# piezo-driver_v0_2-R001.net
KiCad netlist of a schematic drawn in EAGLE
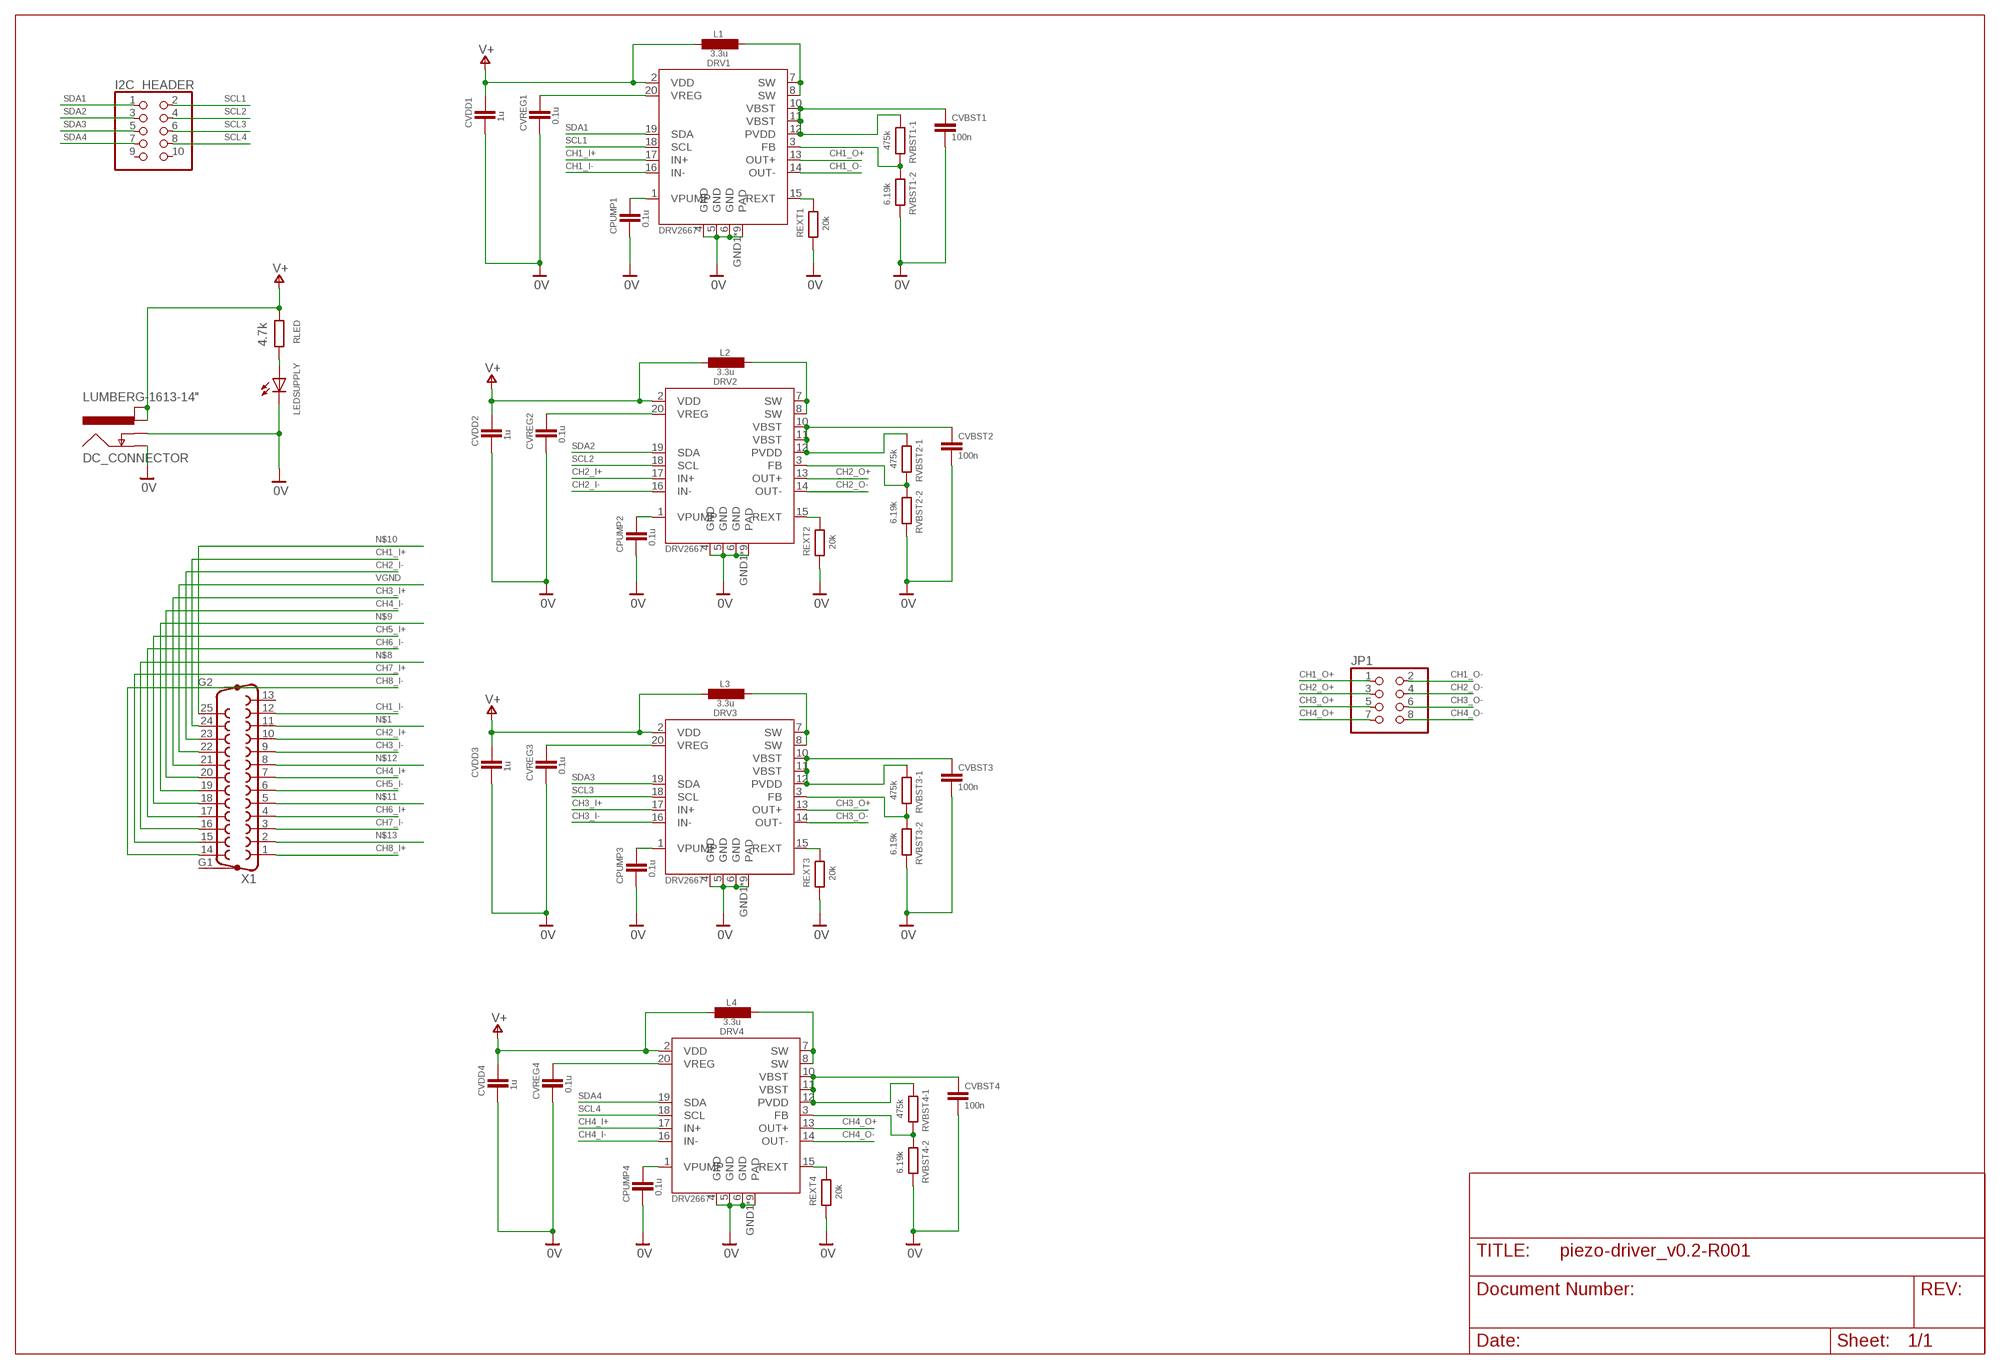
[diagram p0: schematic, sheet 1]

(export (version "E")
  (design (tool "Eeschema 10.0.6"))
  (components
    (comp (ref "CPUMP1")
      (value "0.1u")
      (footprint "eagle-import:C0805")
      (libsource (lib "eagle-import") (part "C-EUC0805"))
    )
    (comp (ref "CPUMP2")
      (value "0.1u")
      (footprint "eagle-import:C0805")
      (libsource (lib "eagle-import") (part "C-EUC0805"))
    )
    (comp (ref "CPUMP3")
      (value "0.1u")
      (footprint "eagle-import:C0805")
      (libsource (lib "eagle-import") (part "C-EUC0805"))
    )
    (comp (ref "CPUMP4")
      (value "0.1u")
      (footprint "eagle-import:C0805")
      (libsource (lib "eagle-import") (part "C-EUC0805"))
    )
    (comp (ref "CVBST1")
      (value "100n")
      (footprint "eagle-import:C0805")
      (libsource (lib "eagle-import") (part "C-EUC0805"))
    )
    (comp (ref "CVBST2")
      (value "100n")
      (footprint "eagle-import:C0805")
      (libsource (lib "eagle-import") (part "C-EUC0805"))
    )
    (comp (ref "CVBST3")
      (value "100n")
      (footprint "eagle-import:C0805")
      (libsource (lib "eagle-import") (part "C-EUC0805"))
    )
    (comp (ref "CVBST4")
      (value "100n")
      (footprint "eagle-import:C0805")
      (libsource (lib "eagle-import") (part "C-EUC0805"))
    )
    (comp (ref "CVDD1")
      (value "1u")
      (footprint "eagle-import:C0805")
      (libsource (lib "eagle-import") (part "C-EUC0805"))
    )
    (comp (ref "CVDD2")
      (value "1u")
      (footprint "eagle-import:C0805")
      (libsource (lib "eagle-import") (part "C-EUC0805"))
    )
    (comp (ref "CVDD3")
      (value "1u")
      (footprint "eagle-import:C0805")
      (libsource (lib "eagle-import") (part "C-EUC0805"))
    )
    (comp (ref "CVDD4")
      (value "1u")
      (footprint "eagle-import:C0805")
      (libsource (lib "eagle-import") (part "C-EUC0805"))
    )
    (comp (ref "CVREG1")
      (value "0.1u")
      (footprint "eagle-import:C0805")
      (libsource (lib "eagle-import") (part "C-EUC0805"))
    )
    (comp (ref "CVREG2")
      (value "0.1u")
      (footprint "eagle-import:C0805")
      (libsource (lib "eagle-import") (part "C-EUC0805"))
    )
    (comp (ref "CVREG3")
      (value "0.1u")
      (footprint "eagle-import:C0805")
      (libsource (lib "eagle-import") (part "C-EUC0805"))
    )
    (comp (ref "CVREG4")
      (value "0.1u")
      (footprint "eagle-import:C0805")
      (libsource (lib "eagle-import") (part "C-EUC0805"))
    )
    (comp (ref "DC_CONNECTOR")
      (value "LUMBERG-1613-14\"")
      (footprint "eagle-import:LUMBERG-1613_14")
      (libsource (lib "eagle-import") (part "LUMBERG-1613-14{dblquote}"))
    )
    (comp (ref "DRV1")
      (value "DRV2667QFN")
      (footprint "eagle-import:QFN400X400")
      (libsource (lib "eagle-import") (part "DRV2667QFN"))
    )
    (comp (ref "DRV2")
      (value "DRV2667QFN")
      (footprint "eagle-import:QFN400X400")
      (libsource (lib "eagle-import") (part "DRV2667QFN"))
    )
    (comp (ref "DRV3")
      (value "DRV2667QFN")
      (footprint "eagle-import:QFN400X400")
      (libsource (lib "eagle-import") (part "DRV2667QFN"))
    )
    (comp (ref "DRV4")
      (value "DRV2667QFN")
      (footprint "eagle-import:QFN400X400")
      (libsource (lib "eagle-import") (part "DRV2667QFN"))
    )
    (comp (ref "I2C_HEADER")
      (value "HEADER_2X52.54_FEMALE")
      (footprint "eagle-import:2X05_2.54")
      (libsource (lib "eagle-import") (part "HEADER_2X52.54_FEMALE"))
    )
    (comp (ref "JP1")
      (value "PINHD-2X4/90")
      (footprint "eagle-import:2X04_90")
      (libsource (lib "eagle-import") (part "PINHD-2X4/90"))
    )
    (comp (ref "L1")
      (value "3.3u")
      (footprint "eagle-import:L3225M")
      (libsource (lib "eagle-import") (part "L-EUL3225M"))
    )
    (comp (ref "L2")
      (value "3.3u")
      (footprint "eagle-import:L3225M")
      (libsource (lib "eagle-import") (part "L-EUL3225M"))
    )
    (comp (ref "L3")
      (value "3.3u")
      (footprint "eagle-import:L3225M")
      (libsource (lib "eagle-import") (part "L-EUL3225M"))
    )
    (comp (ref "L4")
      (value "3.3u")
      (footprint "eagle-import:L3225M")
      (libsource (lib "eagle-import") (part "L-EUL3225M"))
    )
    (comp (ref "LEDSUPPLY")
      (value "LED0603")
      (footprint "eagle-import:LED-0603")
      (libsource (lib "eagle-import") (part "LED0603"))
    )
    (comp (ref "REXT1")
      (value "20k")
      (footprint "eagle-import:R0805")
      (libsource (lib "eagle-import") (part "R-EU_R0805"))
    )
    (comp (ref "REXT2")
      (value "20k")
      (footprint "eagle-import:R0805")
      (libsource (lib "eagle-import") (part "R-EU_R0805"))
    )
    (comp (ref "REXT3")
      (value "20k")
      (footprint "eagle-import:R0805")
      (libsource (lib "eagle-import") (part "R-EU_R0805"))
    )
    (comp (ref "REXT4")
      (value "20k")
      (footprint "eagle-import:R0805")
      (libsource (lib "eagle-import") (part "R-EU_R0805"))
    )
    (comp (ref "RLED")
      (value "4.7k")
      (footprint "eagle-import:R0805")
      (libsource (lib "eagle-import") (part "rcl_R-EU_R0805"))
    )
    (comp (ref "RVBST1-1")
      (value "475k")
      (footprint "eagle-import:R0805")
      (libsource (lib "eagle-import") (part "R-EU_R0805"))
    )
    (comp (ref "RVBST1-2")
      (value "6.19k")
      (footprint "eagle-import:R0805")
      (libsource (lib "eagle-import") (part "R-EU_R0805"))
    )
    (comp (ref "RVBST2-1")
      (value "475k")
      (footprint "eagle-import:R0805")
      (libsource (lib "eagle-import") (part "R-EU_R0805"))
    )
    (comp (ref "RVBST2-2")
      (value "6.19k")
      (footprint "eagle-import:R0805")
      (libsource (lib "eagle-import") (part "R-EU_R0805"))
    )
    (comp (ref "RVBST3-1")
      (value "475k")
      (footprint "eagle-import:R0805")
      (libsource (lib "eagle-import") (part "R-EU_R0805"))
    )
    (comp (ref "RVBST3-2")
      (value "6.19k")
      (footprint "eagle-import:R0805")
      (libsource (lib "eagle-import") (part "R-EU_R0805"))
    )
    (comp (ref "RVBST4-1")
      (value "475k")
      (footprint "eagle-import:R0805")
      (libsource (lib "eagle-import") (part "R-EU_R0805"))
    )
    (comp (ref "RVBST4-2")
      (value "6.19k")
      (footprint "eagle-import:R0805")
      (libsource (lib "eagle-import") (part "R-EU_R0805"))
    )
    (comp (ref "X1")
      (value "F25HP")
      (footprint "eagle-import:F25HP")
      (libsource (lib "eagle-import") (part "F25HP"))
    )
  )
  (nets
    (net (code "1") (name "/CH1_I+") (class "Default")
      (node (ref "DRV1") (pin "17") (pinfunction "IN+_17") (pintype "bidirectional"))
      (node (ref "X1") (pin "24") (pinfunction "24_24") (pintype "passive"))
    )
    (net (code "2") (name "/CH1_I-") (class "Default")
      (node (ref "DRV1") (pin "16") (pinfunction "IN-_16") (pintype "bidirectional"))
      (node (ref "X1") (pin "12") (pinfunction "12_12") (pintype "passive"))
    )
    (net (code "3") (name "/CH1_O+") (class "Default")
      (node (ref "DRV1") (pin "13") (pinfunction "OUT+_13") (pintype "bidirectional"))
      (node (ref "JP1") (pin "1") (pinfunction "1_1") (pintype "passive"))
    )
    (net (code "4") (name "/CH1_O-") (class "Default")
      (node (ref "DRV1") (pin "14") (pinfunction "OUT-_14") (pintype "bidirectional"))
      (node (ref "JP1") (pin "2") (pinfunction "2_2") (pintype "passive"))
    )
    (net (code "5") (name "/CH2_I+") (class "Default")
      (node (ref "DRV2") (pin "17") (pinfunction "IN+_17") (pintype "bidirectional"))
      (node (ref "X1") (pin "10") (pinfunction "10_10") (pintype "passive"))
    )
    (net (code "6") (name "/CH2_I-") (class "Default")
      (node (ref "DRV2") (pin "16") (pinfunction "IN-_16") (pintype "bidirectional"))
      (node (ref "X1") (pin "23") (pinfunction "23_23") (pintype "passive"))
    )
    (net (code "7") (name "/CH2_O+") (class "Default")
      (node (ref "DRV2") (pin "13") (pinfunction "OUT+_13") (pintype "bidirectional"))
      (node (ref "JP1") (pin "3") (pinfunction "3_3") (pintype "passive"))
    )
    (net (code "8") (name "/CH2_O-") (class "Default")
      (node (ref "DRV2") (pin "14") (pinfunction "OUT-_14") (pintype "bidirectional"))
      (node (ref "JP1") (pin "4") (pinfunction "4_4") (pintype "passive"))
    )
    (net (code "9") (name "/CH3_I+") (class "Default")
      (node (ref "DRV3") (pin "17") (pinfunction "IN+_17") (pintype "bidirectional"))
      (node (ref "X1") (pin "21") (pinfunction "21_21") (pintype "passive"))
    )
    (net (code "10") (name "/CH3_I-") (class "Default")
      (node (ref "DRV3") (pin "16") (pinfunction "IN-_16") (pintype "bidirectional"))
      (node (ref "X1") (pin "9") (pinfunction "9_9") (pintype "passive"))
    )
    (net (code "11") (name "/CH3_O+") (class "Default")
      (node (ref "DRV3") (pin "13") (pinfunction "OUT+_13") (pintype "bidirectional"))
      (node (ref "JP1") (pin "5") (pinfunction "5_5") (pintype "passive"))
    )
    (net (code "12") (name "/CH3_O-") (class "Default")
      (node (ref "DRV3") (pin "14") (pinfunction "OUT-_14") (pintype "bidirectional"))
      (node (ref "JP1") (pin "6") (pinfunction "6_6") (pintype "passive"))
    )
    (net (code "13") (name "/CH4_I+") (class "Default")
      (node (ref "DRV4") (pin "17") (pinfunction "IN+_17") (pintype "bidirectional"))
      (node (ref "X1") (pin "7") (pinfunction "7_7") (pintype "passive"))
    )
    (net (code "14") (name "/CH4_I-") (class "Default")
      (node (ref "DRV4") (pin "16") (pinfunction "IN-_16") (pintype "bidirectional"))
      (node (ref "X1") (pin "20") (pinfunction "20_20") (pintype "passive"))
    )
    (net (code "15") (name "/CH4_O+") (class "Default")
      (node (ref "DRV4") (pin "13") (pinfunction "OUT+_13") (pintype "bidirectional"))
      (node (ref "JP1") (pin "7") (pinfunction "7_7") (pintype "passive"))
    )
    (net (code "16") (name "/CH4_O-") (class "Default")
      (node (ref "DRV4") (pin "14") (pinfunction "OUT-_14") (pintype "bidirectional"))
      (node (ref "JP1") (pin "8") (pinfunction "8_8") (pintype "passive"))
    )
    (net (code "17") (name "/CH5_I+") (class "Default")
      (node (ref "X1") (pin "18") (pinfunction "18_18") (pintype "passive"))
    )
    (net (code "18") (name "/CH5_I-") (class "Default")
      (node (ref "X1") (pin "6") (pinfunction "6_6") (pintype "passive"))
    )
    (net (code "19") (name "/CH6_I+") (class "Default")
      (node (ref "X1") (pin "4") (pinfunction "4_4") (pintype "passive"))
    )
    (net (code "20") (name "/CH6_I-") (class "Default")
      (node (ref "X1") (pin "17") (pinfunction "17_17") (pintype "passive"))
    )
    (net (code "21") (name "/CH7_I+") (class "Default")
      (node (ref "X1") (pin "15") (pinfunction "15_15") (pintype "passive"))
    )
    (net (code "22") (name "/CH7_I-") (class "Default")
      (node (ref "X1") (pin "3") (pinfunction "3_3") (pintype "passive"))
    )
    (net (code "23") (name "/CH8_I+") (class "Default")
      (node (ref "X1") (pin "1") (pinfunction "1_1") (pintype "passive"))
    )
    (net (code "24") (name "/CH8_I-") (class "Default")
      (node (ref "X1") (pin "14") (pinfunction "14_14") (pintype "passive"))
    )
    (net (code "25") (name "/N$1") (class "Default")
      (node (ref "X1") (pin "11") (pinfunction "11_11") (pintype "passive"))
    )
    (net (code "26") (name "/N$8") (class "Default")
      (node (ref "X1") (pin "16") (pinfunction "16_16") (pintype "passive"))
    )
    (net (code "27") (name "/N$9") (class "Default")
      (node (ref "X1") (pin "19") (pinfunction "19_19") (pintype "passive"))
    )
    (net (code "28") (name "/N$10") (class "Default")
      (node (ref "X1") (pin "25") (pinfunction "25_25") (pintype "passive"))
    )
    (net (code "29") (name "/N$11") (class "Default")
      (node (ref "X1") (pin "5") (pinfunction "5_5") (pintype "passive"))
    )
    (net (code "30") (name "/N$12") (class "Default")
      (node (ref "X1") (pin "8") (pinfunction "8_8") (pintype "passive"))
    )
    (net (code "31") (name "/N$13") (class "Default")
      (node (ref "X1") (pin "2") (pinfunction "2_2") (pintype "passive"))
    )
    (net (code "32") (name "/SCL1") (class "Default")
      (node (ref "DRV1") (pin "18") (pinfunction "SCL_18") (pintype "bidirectional"))
      (node (ref "I2C_HEADER") (pin "2") (pinfunction "2_2") (pintype "passive"))
    )
    (net (code "33") (name "/SCL2") (class "Default")
      (node (ref "DRV2") (pin "18") (pinfunction "SCL_18") (pintype "bidirectional"))
      (node (ref "I2C_HEADER") (pin "4") (pinfunction "4_4") (pintype "passive"))
    )
    (net (code "34") (name "/SCL3") (class "Default")
      (node (ref "DRV3") (pin "18") (pinfunction "SCL_18") (pintype "bidirectional"))
      (node (ref "I2C_HEADER") (pin "6") (pinfunction "6_6") (pintype "passive"))
    )
    (net (code "35") (name "/SCL4") (class "Default")
      (node (ref "DRV4") (pin "18") (pinfunction "SCL_18") (pintype "bidirectional"))
      (node (ref "I2C_HEADER") (pin "8") (pinfunction "8_8") (pintype "passive"))
    )
    (net (code "36") (name "/SDA1") (class "Default")
      (node (ref "DRV1") (pin "19") (pinfunction "SDA_19") (pintype "bidirectional"))
      (node (ref "I2C_HEADER") (pin "1") (pinfunction "1_1") (pintype "passive"))
    )
    (net (code "37") (name "/SDA2") (class "Default")
      (node (ref "DRV2") (pin "19") (pinfunction "SDA_19") (pintype "bidirectional"))
      (node (ref "I2C_HEADER") (pin "3") (pinfunction "3_3") (pintype "passive"))
    )
    (net (code "38") (name "/SDA3") (class "Default")
      (node (ref "DRV3") (pin "19") (pinfunction "SDA_19") (pintype "bidirectional"))
      (node (ref "I2C_HEADER") (pin "5") (pinfunction "5_5") (pintype "passive"))
    )
    (net (code "39") (name "/SDA4") (class "Default")
      (node (ref "DRV4") (pin "19") (pinfunction "SDA_19") (pintype "bidirectional"))
      (node (ref "I2C_HEADER") (pin "7") (pinfunction "7_7") (pintype "passive"))
    )
    (net (code "40") (name "/VGND") (class "Default")
      (node (ref "X1") (pin "22") (pinfunction "22_22") (pintype "passive"))
    )
    (net (code "41") (name "0V") (class "Default")
      (node (ref "CPUMP1") (pin "2") (pinfunction "2_2") (pintype "passive"))
      (node (ref "CPUMP2") (pin "2") (pinfunction "2_2") (pintype "passive"))
      (node (ref "CPUMP3") (pin "2") (pinfunction "2_2") (pintype "passive"))
      (node (ref "CPUMP4") (pin "2") (pinfunction "2_2") (pintype "passive"))
      (node (ref "CVBST1") (pin "2") (pinfunction "2_2") (pintype "passive"))
      (node (ref "CVBST2") (pin "2") (pinfunction "2_2") (pintype "passive"))
      (node (ref "CVBST3") (pin "2") (pinfunction "2_2") (pintype "passive"))
      (node (ref "CVBST4") (pin "2") (pinfunction "2_2") (pintype "passive"))
      (node (ref "CVDD1") (pin "2") (pinfunction "2_2") (pintype "passive"))
      (node (ref "CVDD2") (pin "2") (pinfunction "2_2") (pintype "passive"))
      (node (ref "CVDD3") (pin "2") (pinfunction "2_2") (pintype "passive"))
      (node (ref "CVDD4") (pin "2") (pinfunction "2_2") (pintype "passive"))
      (node (ref "CVREG1") (pin "2") (pinfunction "2_2") (pintype "passive"))
      (node (ref "CVREG2") (pin "2") (pinfunction "2_2") (pintype "passive"))
      (node (ref "CVREG3") (pin "2") (pinfunction "2_2") (pintype "passive"))
      (node (ref "CVREG4") (pin "2") (pinfunction "2_2") (pintype "passive"))
      (node (ref "DC_CONNECTOR") (pin "1") (pinfunction "GND_1") (pintype "power_in"))
      (node (ref "DC_CONNECTOR") (pin "2") (pinfunction "GND_INS_2") (pintype "power_in"))
      (node (ref "DRV1") (pin "4") (pinfunction "GND_4") (pintype "bidirectional"))
      (node (ref "DRV1") (pin "5") (pinfunction "GND_5") (pintype "bidirectional"))
      (node (ref "DRV1") (pin "6") (pinfunction "GND_6") (pintype "bidirectional"))
      (node (ref "DRV1") (pin "GND1") (pinfunction "PAD_GND1") (pintype "bidirectional"))
      (node (ref "DRV1") (pin "GND2") (pinfunction "PAD_GND2") (pintype "bidirectional"))
      (node (ref "DRV1") (pin "GND3") (pinfunction "PAD_GND3") (pintype "bidirectional"))
      (node (ref "DRV1") (pin "GND4") (pinfunction "PAD_GND4") (pintype "bidirectional"))
      (node (ref "DRV1") (pin "GND5") (pinfunction "PAD_GND5") (pintype "bidirectional"))
      (node (ref "DRV1") (pin "GND6") (pinfunction "PAD_GND6") (pintype "bidirectional"))
      (node (ref "DRV1") (pin "GND7") (pinfunction "PAD_GND7") (pintype "bidirectional"))
      (node (ref "DRV1") (pin "GND8") (pinfunction "PAD_GND8") (pintype "bidirectional"))
      (node (ref "DRV1") (pin "GND9") (pinfunction "PAD_GND9") (pintype "bidirectional"))
      (node (ref "DRV2") (pin "4") (pinfunction "GND_4") (pintype "bidirectional"))
      (node (ref "DRV2") (pin "5") (pinfunction "GND_5") (pintype "bidirectional"))
      (node (ref "DRV2") (pin "6") (pinfunction "GND_6") (pintype "bidirectional"))
      (node (ref "DRV2") (pin "GND1") (pinfunction "PAD_GND1") (pintype "bidirectional"))
      (node (ref "DRV2") (pin "GND2") (pinfunction "PAD_GND2") (pintype "bidirectional"))
      (node (ref "DRV2") (pin "GND3") (pinfunction "PAD_GND3") (pintype "bidirectional"))
      (node (ref "DRV2") (pin "GND4") (pinfunction "PAD_GND4") (pintype "bidirectional"))
      (node (ref "DRV2") (pin "GND5") (pinfunction "PAD_GND5") (pintype "bidirectional"))
      (node (ref "DRV2") (pin "GND6") (pinfunction "PAD_GND6") (pintype "bidirectional"))
      (node (ref "DRV2") (pin "GND7") (pinfunction "PAD_GND7") (pintype "bidirectional"))
      (node (ref "DRV2") (pin "GND8") (pinfunction "PAD_GND8") (pintype "bidirectional"))
      (node (ref "DRV2") (pin "GND9") (pinfunction "PAD_GND9") (pintype "bidirectional"))
      (node (ref "DRV3") (pin "4") (pinfunction "GND_4") (pintype "bidirectional"))
      (node (ref "DRV3") (pin "5") (pinfunction "GND_5") (pintype "bidirectional"))
      (node (ref "DRV3") (pin "6") (pinfunction "GND_6") (pintype "bidirectional"))
      (node (ref "DRV3") (pin "GND1") (pinfunction "PAD_GND1") (pintype "bidirectional"))
      (node (ref "DRV3") (pin "GND2") (pinfunction "PAD_GND2") (pintype "bidirectional"))
      (node (ref "DRV3") (pin "GND3") (pinfunction "PAD_GND3") (pintype "bidirectional"))
      (node (ref "DRV3") (pin "GND4") (pinfunction "PAD_GND4") (pintype "bidirectional"))
      (node (ref "DRV3") (pin "GND5") (pinfunction "PAD_GND5") (pintype "bidirectional"))
      (node (ref "DRV3") (pin "GND6") (pinfunction "PAD_GND6") (pintype "bidirectional"))
      (node (ref "DRV3") (pin "GND7") (pinfunction "PAD_GND7") (pintype "bidirectional"))
      (node (ref "DRV3") (pin "GND8") (pinfunction "PAD_GND8") (pintype "bidirectional"))
      (node (ref "DRV3") (pin "GND9") (pinfunction "PAD_GND9") (pintype "bidirectional"))
      (node (ref "DRV4") (pin "4") (pinfunction "GND_4") (pintype "bidirectional"))
      (node (ref "DRV4") (pin "5") (pinfunction "GND_5") (pintype "bidirectional"))
      (node (ref "DRV4") (pin "6") (pinfunction "GND_6") (pintype "bidirectional"))
      (node (ref "DRV4") (pin "GND1") (pinfunction "PAD_GND1") (pintype "bidirectional"))
      (node (ref "DRV4") (pin "GND2") (pinfunction "PAD_GND2") (pintype "bidirectional"))
      (node (ref "DRV4") (pin "GND3") (pinfunction "PAD_GND3") (pintype "bidirectional"))
      (node (ref "DRV4") (pin "GND4") (pinfunction "PAD_GND4") (pintype "bidirectional"))
      (node (ref "DRV4") (pin "GND5") (pinfunction "PAD_GND5") (pintype "bidirectional"))
      (node (ref "DRV4") (pin "GND6") (pinfunction "PAD_GND6") (pintype "bidirectional"))
      (node (ref "DRV4") (pin "GND7") (pinfunction "PAD_GND7") (pintype "bidirectional"))
      (node (ref "DRV4") (pin "GND8") (pinfunction "PAD_GND8") (pintype "bidirectional"))
      (node (ref "DRV4") (pin "GND9") (pinfunction "PAD_GND9") (pintype "bidirectional"))
      (node (ref "LEDSUPPLY") (pin "C") (pinfunction "C_C") (pintype "passive"))
      (node (ref "REXT1") (pin "1") (pinfunction "1_1") (pintype "passive"))
      (node (ref "REXT2") (pin "1") (pinfunction "1_1") (pintype "passive"))
      (node (ref "REXT3") (pin "1") (pinfunction "1_1") (pintype "passive"))
      (node (ref "REXT4") (pin "1") (pinfunction "1_1") (pintype "passive"))
      (node (ref "RVBST1-2") (pin "1") (pinfunction "1_1") (pintype "passive"))
      (node (ref "RVBST2-2") (pin "1") (pinfunction "1_1") (pintype "passive"))
      (node (ref "RVBST3-2") (pin "1") (pinfunction "1_1") (pintype "passive"))
      (node (ref "RVBST4-2") (pin "1") (pinfunction "1_1") (pintype "passive"))
    )
    (net (code "42") (name "Net-(DRV1-FB)") (class "Default")
      (node (ref "DRV1") (pin "3") (pinfunction "FB_3") (pintype "bidirectional"))
      (node (ref "RVBST1-1") (pin "1") (pinfunction "1_1") (pintype "passive"))
      (node (ref "RVBST1-2") (pin "2") (pinfunction "2_2") (pintype "passive"))
    )
    (net (code "43") (name "Net-(DRV1-PVDD)") (class "Default")
      (node (ref "CVBST1") (pin "1") (pinfunction "1_1") (pintype "passive"))
      (node (ref "DRV1") (pin "10") (pinfunction "VBST_10") (pintype "bidirectional"))
      (node (ref "DRV1") (pin "11") (pinfunction "VBST_11") (pintype "bidirectional"))
      (node (ref "DRV1") (pin "12") (pinfunction "PVDD_12") (pintype "bidirectional"))
      (node (ref "RVBST1-1") (pin "2") (pinfunction "2_2") (pintype "passive"))
    )
    (net (code "44") (name "Net-(DRV1-REXT)") (class "Default")
      (node (ref "DRV1") (pin "15") (pinfunction "REXT_15") (pintype "bidirectional"))
      (node (ref "REXT1") (pin "2") (pinfunction "2_2") (pintype "passive"))
    )
    (net (code "45") (name "Net-(DRV1-SW-Pad7)") (class "Default")
      (node (ref "DRV1") (pin "7") (pinfunction "SW_7") (pintype "bidirectional"))
      (node (ref "DRV1") (pin "8") (pinfunction "SW_8") (pintype "bidirectional"))
      (node (ref "L1") (pin "1") (pinfunction "1_1") (pintype "passive"))
    )
    (net (code "46") (name "Net-(DRV1-VPUMP)") (class "Default")
      (node (ref "CPUMP1") (pin "1") (pinfunction "1_1") (pintype "passive"))
      (node (ref "DRV1") (pin "1") (pinfunction "VPUMP_1") (pintype "bidirectional"))
    )
    (net (code "47") (name "Net-(DRV1-VREG)") (class "Default")
      (node (ref "CVREG1") (pin "1") (pinfunction "1_1") (pintype "passive"))
      (node (ref "DRV1") (pin "20") (pinfunction "VREG_20") (pintype "bidirectional"))
    )
    (net (code "48") (name "Net-(DRV2-FB)") (class "Default")
      (node (ref "DRV2") (pin "3") (pinfunction "FB_3") (pintype "bidirectional"))
      (node (ref "RVBST2-1") (pin "1") (pinfunction "1_1") (pintype "passive"))
      (node (ref "RVBST2-2") (pin "2") (pinfunction "2_2") (pintype "passive"))
    )
    (net (code "49") (name "Net-(DRV2-PVDD)") (class "Default")
      (node (ref "CVBST2") (pin "1") (pinfunction "1_1") (pintype "passive"))
      (node (ref "DRV2") (pin "10") (pinfunction "VBST_10") (pintype "bidirectional"))
      (node (ref "DRV2") (pin "11") (pinfunction "VBST_11") (pintype "bidirectional"))
      (node (ref "DRV2") (pin "12") (pinfunction "PVDD_12") (pintype "bidirectional"))
      (node (ref "RVBST2-1") (pin "2") (pinfunction "2_2") (pintype "passive"))
    )
    (net (code "50") (name "Net-(DRV2-REXT)") (class "Default")
      (node (ref "DRV2") (pin "15") (pinfunction "REXT_15") (pintype "bidirectional"))
      (node (ref "REXT2") (pin "2") (pinfunction "2_2") (pintype "passive"))
    )
    (net (code "51") (name "Net-(DRV2-SW-Pad7)") (class "Default")
      (node (ref "DRV2") (pin "7") (pinfunction "SW_7") (pintype "bidirectional"))
      (node (ref "DRV2") (pin "8") (pinfunction "SW_8") (pintype "bidirectional"))
      (node (ref "L2") (pin "1") (pinfunction "1_1") (pintype "passive"))
    )
    (net (code "52") (name "Net-(DRV2-VPUMP)") (class "Default")
      (node (ref "CPUMP2") (pin "1") (pinfunction "1_1") (pintype "passive"))
      (node (ref "DRV2") (pin "1") (pinfunction "VPUMP_1") (pintype "bidirectional"))
    )
    (net (code "53") (name "Net-(DRV2-VREG)") (class "Default")
      (node (ref "CVREG2") (pin "1") (pinfunction "1_1") (pintype "passive"))
      (node (ref "DRV2") (pin "20") (pinfunction "VREG_20") (pintype "bidirectional"))
    )
    (net (code "54") (name "Net-(DRV3-FB)") (class "Default")
      (node (ref "DRV3") (pin "3") (pinfunction "FB_3") (pintype "bidirectional"))
      (node (ref "RVBST3-1") (pin "1") (pinfunction "1_1") (pintype "passive"))
      (node (ref "RVBST3-2") (pin "2") (pinfunction "2_2") (pintype "passive"))
    )
    (net (code "55") (name "Net-(DRV3-PVDD)") (class "Default")
      (node (ref "CVBST3") (pin "1") (pinfunction "1_1") (pintype "passive"))
      (node (ref "DRV3") (pin "10") (pinfunction "VBST_10") (pintype "bidirectional"))
      (node (ref "DRV3") (pin "11") (pinfunction "VBST_11") (pintype "bidirectional"))
      (node (ref "DRV3") (pin "12") (pinfunction "PVDD_12") (pintype "bidirectional"))
      (node (ref "RVBST3-1") (pin "2") (pinfunction "2_2") (pintype "passive"))
    )
    (net (code "56") (name "Net-(DRV3-REXT)") (class "Default")
      (node (ref "DRV3") (pin "15") (pinfunction "REXT_15") (pintype "bidirectional"))
      (node (ref "REXT3") (pin "2") (pinfunction "2_2") (pintype "passive"))
    )
    (net (code "57") (name "Net-(DRV3-SW-Pad7)") (class "Default")
      (node (ref "DRV3") (pin "7") (pinfunction "SW_7") (pintype "bidirectional"))
      (node (ref "DRV3") (pin "8") (pinfunction "SW_8") (pintype "bidirectional"))
      (node (ref "L3") (pin "1") (pinfunction "1_1") (pintype "passive"))
    )
    (net (code "58") (name "Net-(DRV3-VPUMP)") (class "Default")
      (node (ref "CPUMP3") (pin "1") (pinfunction "1_1") (pintype "passive"))
      (node (ref "DRV3") (pin "1") (pinfunction "VPUMP_1") (pintype "bidirectional"))
    )
    (net (code "59") (name "Net-(DRV3-VREG)") (class "Default")
      (node (ref "CVREG3") (pin "1") (pinfunction "1_1") (pintype "passive"))
      (node (ref "DRV3") (pin "20") (pinfunction "VREG_20") (pintype "bidirectional"))
    )
    (net (code "60") (name "Net-(DRV4-FB)") (class "Default")
      (node (ref "DRV4") (pin "3") (pinfunction "FB_3") (pintype "bidirectional"))
      (node (ref "RVBST4-1") (pin "1") (pinfunction "1_1") (pintype "passive"))
      (node (ref "RVBST4-2") (pin "2") (pinfunction "2_2") (pintype "passive"))
    )
    (net (code "61") (name "Net-(DRV4-PVDD)") (class "Default")
      (node (ref "CVBST4") (pin "1") (pinfunction "1_1") (pintype "passive"))
      (node (ref "DRV4") (pin "10") (pinfunction "VBST_10") (pintype "bidirectional"))
      (node (ref "DRV4") (pin "11") (pinfunction "VBST_11") (pintype "bidirectional"))
      (node (ref "DRV4") (pin "12") (pinfunction "PVDD_12") (pintype "bidirectional"))
      (node (ref "RVBST4-1") (pin "2") (pinfunction "2_2") (pintype "passive"))
    )
    (net (code "62") (name "Net-(DRV4-REXT)") (class "Default")
      (node (ref "DRV4") (pin "15") (pinfunction "REXT_15") (pintype "bidirectional"))
      (node (ref "REXT4") (pin "2") (pinfunction "2_2") (pintype "passive"))
    )
    (net (code "63") (name "Net-(DRV4-SW-Pad7)") (class "Default")
      (node (ref "DRV4") (pin "7") (pinfunction "SW_7") (pintype "bidirectional"))
      (node (ref "DRV4") (pin "8") (pinfunction "SW_8") (pintype "bidirectional"))
      (node (ref "L4") (pin "1") (pinfunction "1_1") (pintype "passive"))
    )
    (net (code "64") (name "Net-(DRV4-VPUMP)") (class "Default")
      (node (ref "CPUMP4") (pin "1") (pinfunction "1_1") (pintype "passive"))
      (node (ref "DRV4") (pin "1") (pinfunction "VPUMP_1") (pintype "bidirectional"))
    )
    (net (code "65") (name "Net-(DRV4-VREG)") (class "Default")
      (node (ref "CVREG4") (pin "1") (pinfunction "1_1") (pintype "passive"))
      (node (ref "DRV4") (pin "20") (pinfunction "VREG_20") (pintype "bidirectional"))
    )
    (net (code "66") (name "Net-(LEDSUPPLY-PadA)") (class "Default")
      (node (ref "LEDSUPPLY") (pin "A") (pinfunction "A_A") (pintype "passive"))
      (node (ref "RLED") (pin "1") (pinfunction "1_1") (pintype "passive"))
    )
    (net (code "67") (name "V+") (class "Default")
      (node (ref "CVDD1") (pin "1") (pinfunction "1_1") (pintype "passive"))
      (node (ref "CVDD2") (pin "1") (pinfunction "1_1") (pintype "passive"))
      (node (ref "CVDD3") (pin "1") (pinfunction "1_1") (pintype "passive"))
      (node (ref "CVDD4") (pin "1") (pinfunction "1_1") (pintype "passive"))
      (node (ref "DC_CONNECTOR") (pin "3") (pinfunction "PWR_1_3") (pintype "power_in"))
      (node (ref "DC_CONNECTOR") (pin "4") (pinfunction "PWR_2_4") (pintype "power_in"))
      (node (ref "DRV1") (pin "2") (pinfunction "VDD_2") (pintype "bidirectional"))
      (node (ref "DRV2") (pin "2") (pinfunction "VDD_2") (pintype "bidirectional"))
      (node (ref "DRV3") (pin "2") (pinfunction "VDD_2") (pintype "bidirectional"))
      (node (ref "DRV4") (pin "2") (pinfunction "VDD_2") (pintype "bidirectional"))
      (node (ref "L1") (pin "2") (pinfunction "2_2") (pintype "passive"))
      (node (ref "L2") (pin "2") (pinfunction "2_2") (pintype "passive"))
      (node (ref "L3") (pin "2") (pinfunction "2_2") (pintype "passive"))
      (node (ref "L4") (pin "2") (pinfunction "2_2") (pintype "passive"))
      (node (ref "RLED") (pin "2") (pinfunction "2_2") (pintype "passive"))
    )
    (net (code "68") (name "unconnected-(I2C_HEADER-Pad9)") (class "Default")
      (node (ref "I2C_HEADER") (pin "9") (pinfunction "9_9") (pintype "passive"))
    )
    (net (code "69") (name "unconnected-(I2C_HEADER-Pad10)") (class "Default")
      (node (ref "I2C_HEADER") (pin "10") (pinfunction "10_10") (pintype "passive"))
    )
    (net (code "70") (name "unconnected-(X1-Pad13)") (class "Default")
      (node (ref "X1") (pin "13") (pinfunction "13_13") (pintype "passive"))
    )
    (net (code "71") (name "unconnected-(X1-PadG1)") (class "Default")
      (node (ref "X1") (pin "G1") (pinfunction "G1_G1") (pintype "passive"))
    )
    (net (code "72") (name "unconnected-(X1-PadG2)") (class "Default")
      (node (ref "X1") (pin "G2") (pinfunction "G2_G2") (pintype "passive"))
    )
  )
)
